# VoltageReferenceProgrammableRevD.net
KiCad netlist of a schematic drawn in EAGLE
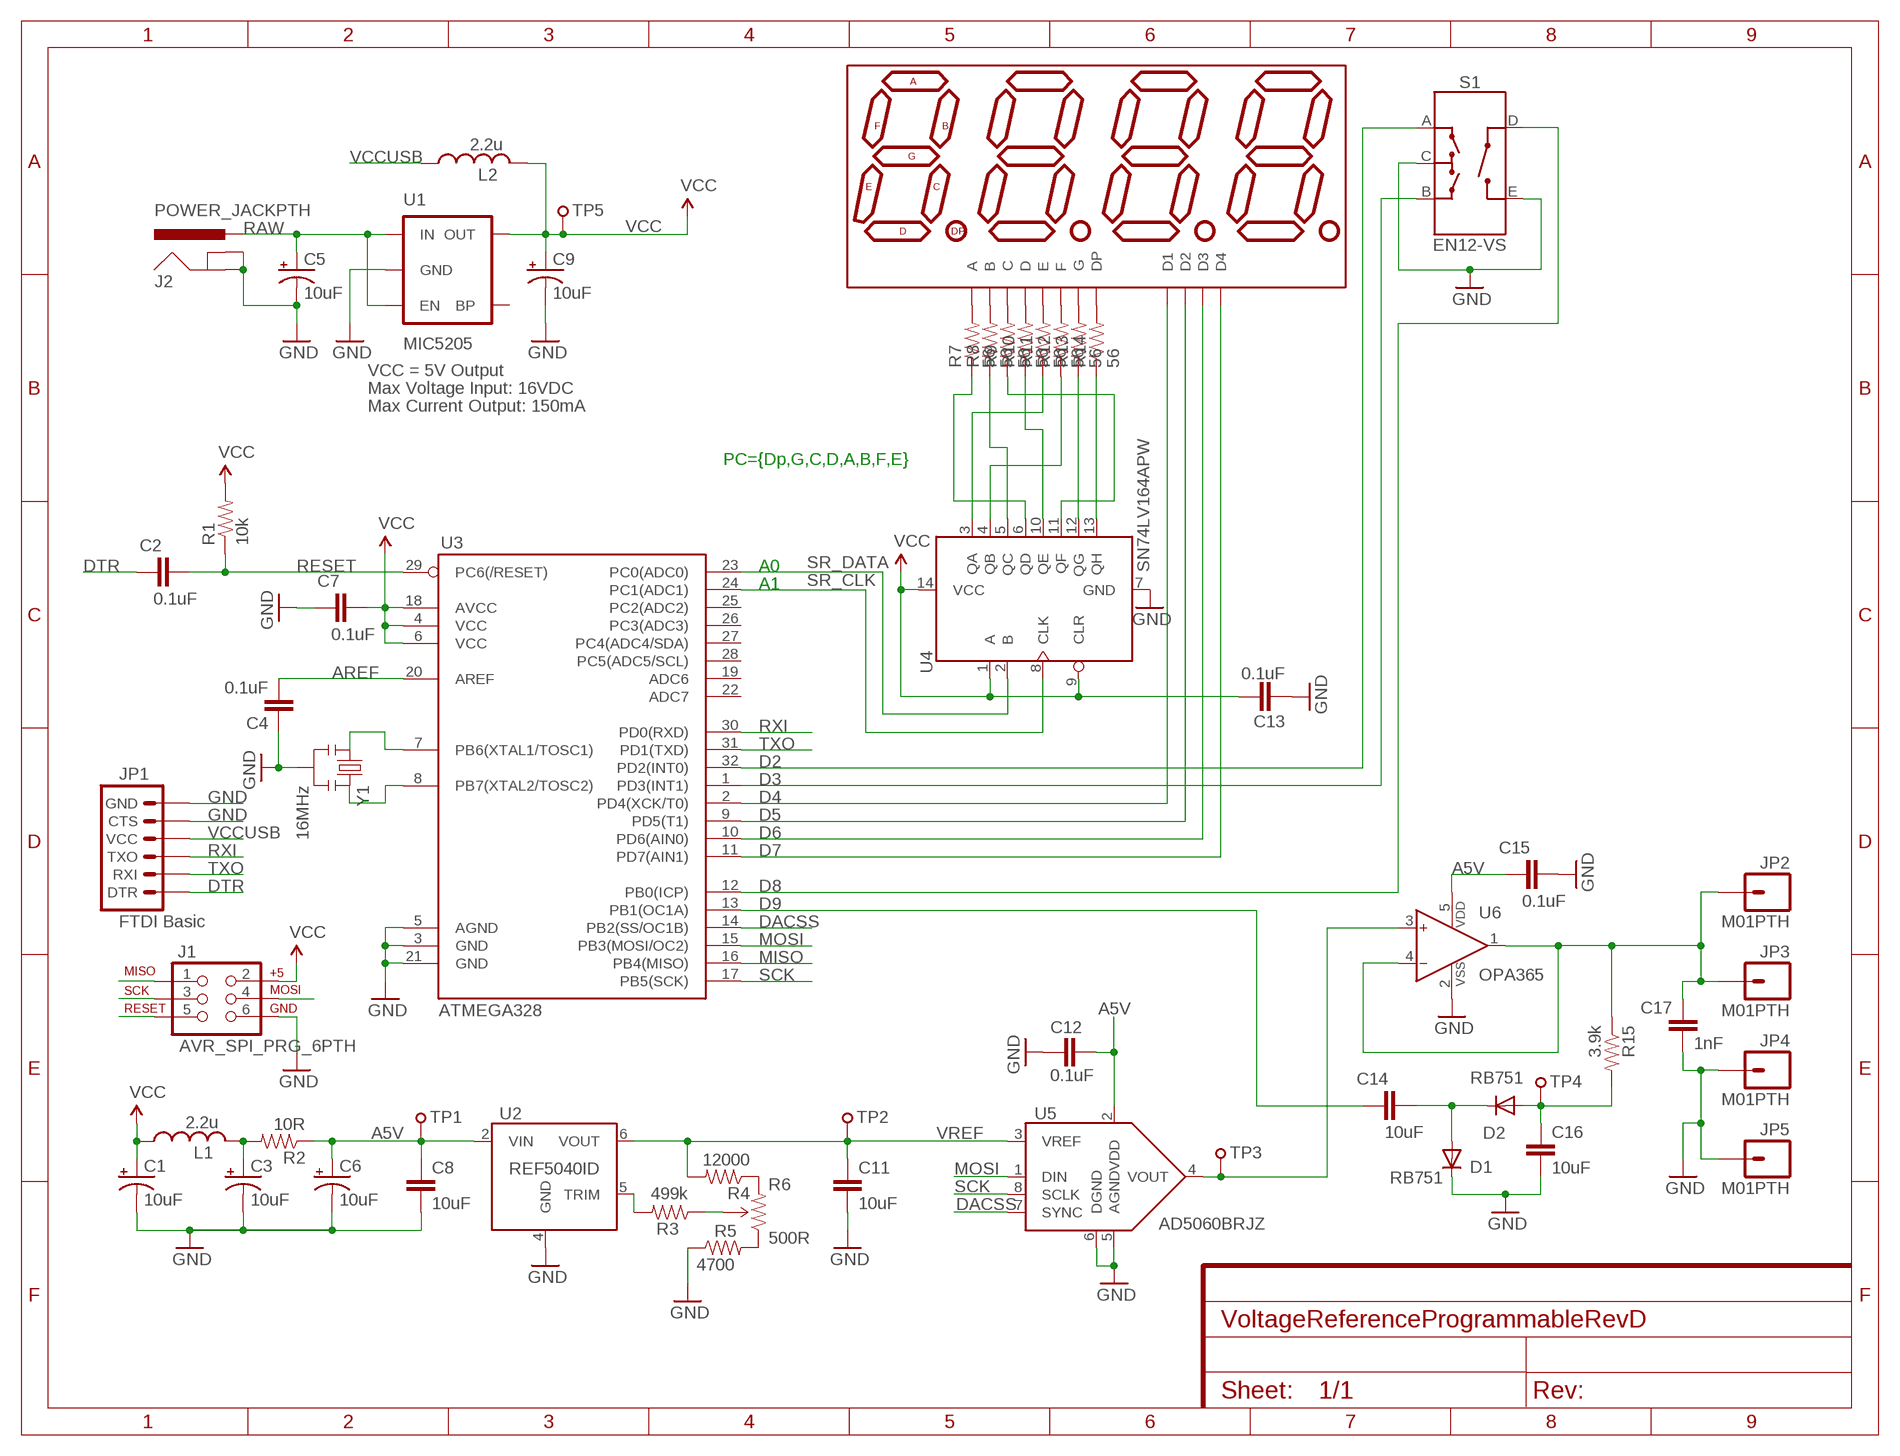
[diagram p0: schematic, sheet 1]

(export (version "E")
  (design (tool "Eeschema 10.0.6"))
  (components
    (comp (ref "C1")
      (value "10uF")
      (footprint "eagle-import:0805-POL")
      (libsource (lib "eagle-import") (part "CAP_POL0805"))
    )
    (comp (ref "C2")
      (value "0.1uF")
      (footprint "eagle-import:0805")
      (libsource (lib "eagle-import") (part "CAP0805"))
    )
    (comp (ref "C3")
      (value "10uF")
      (footprint "eagle-import:0805-POL")
      (libsource (lib "eagle-import") (part "CAP_POL0805"))
    )
    (comp (ref "C4")
      (value "0.1uF")
      (footprint "eagle-import:0805")
      (libsource (lib "eagle-import") (part "CAP0805"))
    )
    (comp (ref "C5")
      (value "10uF")
      (footprint "eagle-import:0805-POL")
      (libsource (lib "eagle-import") (part "CAP_POL0805"))
    )
    (comp (ref "C6")
      (value "10uF")
      (footprint "eagle-import:0805-POL")
      (libsource (lib "eagle-import") (part "CAP_POL0805"))
    )
    (comp (ref "C7")
      (value "0.1uF")
      (footprint "eagle-import:0805")
      (libsource (lib "eagle-import") (part "CAP0805"))
    )
    (comp (ref "C8")
      (value "10uF")
      (footprint "eagle-import:0805")
      (libsource (lib "eagle-import") (part "CAP0805"))
    )
    (comp (ref "C9")
      (value "10uF")
      (footprint "eagle-import:0805-POL")
      (libsource (lib "eagle-import") (part "CAP_POL0805"))
    )
    (comp (ref "C11")
      (value "10uF")
      (footprint "eagle-import:0805")
      (libsource (lib "eagle-import") (part "CAP0805"))
    )
    (comp (ref "C12")
      (value "0.1uF")
      (footprint "eagle-import:0805")
      (libsource (lib "eagle-import") (part "CAP0805"))
    )
    (comp (ref "C13")
      (value "0.1uF")
      (footprint "eagle-import:0805")
      (libsource (lib "eagle-import") (part "CAP0805"))
    )
    (comp (ref "C14")
      (value "10uF")
      (footprint "eagle-import:0805")
      (libsource (lib "eagle-import") (part "CAP0805"))
    )
    (comp (ref "C15")
      (value "0.1uF")
      (footprint "eagle-import:0805")
      (libsource (lib "eagle-import") (part "CAP0805"))
    )
    (comp (ref "C16")
      (value "10uF")
      (footprint "eagle-import:0805")
      (libsource (lib "eagle-import") (part "CAP0805"))
    )
    (comp (ref "C17")
      (value "1nF")
      (footprint "eagle-import:0805")
      (libsource (lib "eagle-import") (part "CAP0805"))
    )
    (comp (ref "D1")
      (value "RB751")
      (footprint "eagle-import:SOD-323")
      (libsource (lib "eagle-import") (part "DIODESOD"))
    )
    (comp (ref "D2")
      (value "RB751")
      (footprint "eagle-import:SOD-323")
      (libsource (lib "eagle-import") (part "DIODESOD"))
    )
    (comp (ref "DISP1")
      (value "hp")
      (footprint "eagle-import:DIL12")
      (libsource (lib "eagle-import") (part "7-SEGMENT-4DIGIT-COUNTER-HP-BUBBLE"))
    )
    (comp (ref "FRAME1")
      (value "FRAME_LTR_CU_MARK")
      (footprint "eagle-import:FR-LTR-ON-PCB")
      (fields
        (field (name "CNAME") "C.Schnarel")
        (field (name "CREVISION") "ProgVRef Rev-D")
        (field (name "DESIGNER") "C.Schnarel")
      )
      (libsource (lib "eagle-import") (part "FRAME_LTR_CU_MARK"))
    )
    (comp (ref "J1")
      (value "AVR_SPI_PRG_6PTH")
      (footprint "eagle-import:2X3")
      (libsource (lib "eagle-import") (part "AVR_SPI_PRG_6PTH"))
    )
    (comp (ref "J2")
      (value "POWER_JACKPTH")
      (footprint "eagle-import:POWER_JACK_PTH")
      (libsource (lib "eagle-import") (part "POWER_JACKPTH"))
    )
    (comp (ref "JP1")
      (value "FTDI Basic")
      (footprint "eagle-import:1X06")
      (libsource (lib "eagle-import") (part "ARDUINO_SERIAL_PROGRAMPTH"))
    )
    (comp (ref "JP2")
      (value "M01PTH")
      (footprint "eagle-import:1X01")
      (libsource (lib "eagle-import") (part "M01PTH"))
    )
    (comp (ref "JP3")
      (value "M01PTH")
      (footprint "eagle-import:1X01")
      (libsource (lib "eagle-import") (part "M01PTH"))
    )
    (comp (ref "JP4")
      (value "M01PTH")
      (footprint "eagle-import:1X01")
      (libsource (lib "eagle-import") (part "M01PTH"))
    )
    (comp (ref "JP5")
      (value "M01PTH")
      (footprint "eagle-import:1X01")
      (libsource (lib "eagle-import") (part "M01PTH"))
    )
    (comp (ref "L1")
      (value "2.2u")
      (footprint "eagle-import:0805")
      (libsource (lib "eagle-import") (part "INDUCTOR"))
    )
    (comp (ref "L2")
      (value "2.2u")
      (footprint "eagle-import:0805")
      (libsource (lib "eagle-import") (part "INDUCTOR"))
    )
    (comp (ref "R1")
      (value "10k")
      (footprint "eagle-import:0805")
      (libsource (lib "eagle-import") (part "RESISTOR0805-RES"))
    )
    (comp (ref "R2")
      (value "10R")
      (footprint "eagle-import:0805")
      (libsource (lib "eagle-import") (part "RESISTOR0805-RES"))
    )
    (comp (ref "R3")
      (value "499k")
      (footprint "eagle-import:0805")
      (libsource (lib "eagle-import") (part "RESISTOR0805-RES"))
    )
    (comp (ref "R4")
      (value "12000")
      (footprint "eagle-import:0805")
      (libsource (lib "eagle-import") (part "RESISTOR0805-RES"))
    )
    (comp (ref "R5")
      (value "4700")
      (footprint "eagle-import:0805")
      (libsource (lib "eagle-import") (part "RESISTOR0805-RES"))
    )
    (comp (ref "R6")
      (value "500R")
      (footprint "eagle-import:T93YB")
      (libsource (lib "eagle-import") (part "TRIMPOT"))
    )
    (comp (ref "R7")
      (value "56")
      (footprint "eagle-import:0805")
      (libsource (lib "eagle-import") (part "RESISTOR0805-RES"))
    )
    (comp (ref "R8")
      (value "56")
      (footprint "eagle-import:0805")
      (libsource (lib "eagle-import") (part "RESISTOR0805-RES"))
    )
    (comp (ref "R9")
      (value "56")
      (footprint "eagle-import:0805")
      (libsource (lib "eagle-import") (part "RESISTOR0805-RES"))
    )
    (comp (ref "R10")
      (value "56")
      (footprint "eagle-import:0805")
      (libsource (lib "eagle-import") (part "RESISTOR0805-RES"))
    )
    (comp (ref "R11")
      (value "56")
      (footprint "eagle-import:0805")
      (libsource (lib "eagle-import") (part "RESISTOR0805-RES"))
    )
    (comp (ref "R12")
      (value "56")
      (footprint "eagle-import:0805")
      (libsource (lib "eagle-import") (part "RESISTOR0805-RES"))
    )
    (comp (ref "R13")
      (value "56")
      (footprint "eagle-import:0805")
      (libsource (lib "eagle-import") (part "RESISTOR0805-RES"))
    )
    (comp (ref "R14")
      (value "56")
      (footprint "eagle-import:0805")
      (libsource (lib "eagle-import") (part "RESISTOR0805-RES"))
    )
    (comp (ref "R15")
      (value "3.9k")
      (footprint "eagle-import:0805")
      (libsource (lib "eagle-import") (part "RESISTOR0805-RES"))
    )
    (comp (ref "S1")
      (value "EN12-VS")
      (footprint "eagle-import:ROTARY_ENCODER_SIDE")
      (libsource (lib "eagle-import") (part "EN12-VS"))
    )
    (comp (ref "TP1")
      (value "TEST_POINT")
      (footprint "eagle-import:BBD-VIA")
      (libsource (lib "eagle-import") (part "TEST_POINT"))
    )
    (comp (ref "TP2")
      (value "TEST_POINT")
      (footprint "eagle-import:BBD-VIA")
      (libsource (lib "eagle-import") (part "TEST_POINT"))
    )
    (comp (ref "TP3")
      (value "TEST_POINT")
      (footprint "eagle-import:BBD-VIA")
      (libsource (lib "eagle-import") (part "TEST_POINT"))
    )
    (comp (ref "TP4")
      (value "TEST_POINT")
      (footprint "eagle-import:BBD-VIA")
      (libsource (lib "eagle-import") (part "TEST_POINT"))
    )
    (comp (ref "TP5")
      (value "TEST_POINT")
      (footprint "eagle-import:BBD-VIA")
      (libsource (lib "eagle-import") (part "TEST_POINT"))
    )
    (comp (ref "U1")
      (value "MIC5205")
      (footprint "eagle-import:SOT23-5")
      (libsource (lib "eagle-import") (part "V_REG_LDOSMD"))
    )
    (comp (ref "U2")
      (value "REF5040ID")
      (footprint "eagle-import:SOIC-8-MINUSPINS")
      (libsource (lib "eagle-import") (part "REF5040ID"))
    )
    (comp (ref "U3")
      (value "ATMEGA328")
      (footprint "eagle-import:TQFP32-08")
      (libsource (lib "eagle-import") (part "ATMEGA168"))
    )
    (comp (ref "U4")
      (value "SN74LV164APW")
      (footprint "eagle-import:TSSOP-14(TI)")
      (libsource (lib "eagle-import") (part "SN74LV164APW"))
    )
    (comp (ref "U5")
      (value "AD5060BRJZ")
      (footprint "eagle-import:SOT-23-8")
      (libsource (lib "eagle-import") (part "AD5040BRJZ"))
    )
    (comp (ref "U6")
      (value "OPA365")
      (footprint "eagle-import:SOT-23-5")
      (libsource (lib "eagle-import") (part "OPA365"))
    )
    (comp (ref "Y1")
      (value "16MHz")
      (footprint "eagle-import:RESONATOR-SMD")
      (libsource (lib "eagle-import") (part "RESONATORSMD"))
    )
  )
  (nets
    (net (code "1") (name "/A5V") (class "Default")
      (node (ref "C12") (pin "1") (pinfunction "1_1") (pintype "passive"))
      (node (ref "C15") (pin "1") (pinfunction "1_1") (pintype "passive"))
      (node (ref "C6") (pin "1") (pinfunction "+_1") (pintype "passive"))
      (node (ref "C8") (pin "1") (pinfunction "1_1") (pintype "passive"))
      (node (ref "R2") (pin "1") (pinfunction "1_1") (pintype "passive"))
      (node (ref "TP1") (pin "P$1") (pinfunction "P$1_P$1") (pintype "bidirectional"))
      (node (ref "U2") (pin "2") (pinfunction "VIN_2") (pintype "bidirectional"))
      (node (ref "U5") (pin "2") (pinfunction "VDD_2") (pintype "bidirectional"))
      (node (ref "U6") (pin "5") (pinfunction "VDD_5") (pintype "power_in"))
    )
    (net (code "2") (name "/AREF") (class "Default")
      (node (ref "C4") (pin "2") (pinfunction "2_2") (pintype "passive"))
      (node (ref "U3") (pin "20") (pinfunction "AREF_20") (pintype "bidirectional"))
    )
    (net (code "3") (name "/D2") (class "Default")
      (node (ref "S1") (pin "A") (pinfunction "A_A") (pintype "bidirectional"))
      (node (ref "U3") (pin "32") (pinfunction "PD2(INT0)_32") (pintype "bidirectional"))
    )
    (net (code "4") (name "/D3") (class "Default")
      (node (ref "S1") (pin "B") (pinfunction "B_B") (pintype "bidirectional"))
      (node (ref "U3") (pin "1") (pinfunction "PD3(INT1)_1") (pintype "bidirectional"))
    )
    (net (code "5") (name "/D4") (class "Default")
      (node (ref "DISP1") (pin "1") (pinfunction "D1_1") (pintype "bidirectional"))
      (node (ref "U3") (pin "2") (pinfunction "PD4(XCK/T0)_2") (pintype "bidirectional"))
    )
    (net (code "6") (name "/D5") (class "Default")
      (node (ref "DISP1") (pin "10") (pinfunction "D2_10") (pintype "bidirectional"))
      (node (ref "U3") (pin "9") (pinfunction "PD5(T1)_9") (pintype "bidirectional"))
    )
    (net (code "7") (name "/D6") (class "Default")
      (node (ref "DISP1") (pin "4") (pinfunction "D3_4") (pintype "bidirectional"))
      (node (ref "U3") (pin "10") (pinfunction "PD6(AIN0)_10") (pintype "bidirectional"))
    )
    (net (code "8") (name "/D7") (class "Default")
      (node (ref "DISP1") (pin "6") (pinfunction "D4_6") (pintype "bidirectional"))
      (node (ref "U3") (pin "11") (pinfunction "PD7(AIN1)_11") (pintype "bidirectional"))
    )
    (net (code "9") (name "/D8") (class "Default")
      (node (ref "S1") (pin "D") (pinfunction "P$1_D") (pintype "bidirectional"))
      (node (ref "U3") (pin "12") (pinfunction "PB0(ICP)_12") (pintype "bidirectional"))
    )
    (net (code "10") (name "/D9") (class "Default")
      (node (ref "C14") (pin "1") (pinfunction "1_1") (pintype "passive"))
      (node (ref "U3") (pin "13") (pinfunction "PB1(OC1A)_13") (pintype "bidirectional"))
    )
    (net (code "11") (name "/DACSS") (class "Default")
      (node (ref "U3") (pin "14") (pinfunction "PB2(SS/OC1B)_14") (pintype "bidirectional"))
      (node (ref "U5") (pin "7") (pinfunction "SYNC_7") (pintype "bidirectional"))
    )
    (net (code "12") (name "/DTR") (class "Default")
      (node (ref "C2") (pin "1") (pinfunction "1_1") (pintype "passive"))
      (node (ref "JP1") (pin "1") (pinfunction "DTR_1") (pintype "passive"))
    )
    (net (code "13") (name "/MISO") (class "Default")
      (node (ref "J1") (pin "1") (pinfunction "1_1") (pintype "passive"))
      (node (ref "U3") (pin "16") (pinfunction "PB4(MISO)_16") (pintype "bidirectional"))
    )
    (net (code "14") (name "/MOSI") (class "Default")
      (node (ref "J1") (pin "4") (pinfunction "4_4") (pintype "passive"))
      (node (ref "U3") (pin "15") (pinfunction "PB3(MOSI/OC2)_15") (pintype "bidirectional"))
      (node (ref "U5") (pin "1") (pinfunction "DIN_1") (pintype "bidirectional"))
    )
    (net (code "15") (name "/RAW") (class "Default")
      (node (ref "C5") (pin "1") (pinfunction "+_1") (pintype "passive"))
      (node (ref "J2") (pin "PWR") (pinfunction "PWR_PWR") (pintype "bidirectional"))
      (node (ref "U1") (pin "1") (pinfunction "IN_1") (pintype "input"))
      (node (ref "U1") (pin "3") (pinfunction "EN_3") (pintype "input"))
    )
    (net (code "16") (name "/RESET") (class "Default")
      (node (ref "C2") (pin "2") (pinfunction "2_2") (pintype "passive"))
      (node (ref "J1") (pin "5") (pinfunction "5_5") (pintype "passive"))
      (node (ref "R1") (pin "1") (pinfunction "1_1") (pintype "passive"))
      (node (ref "U3") (pin "29") (pinfunction "PC6(/RESET)_29") (pintype "bidirectional"))
    )
    (net (code "17") (name "/RXI") (class "Default")
      (node (ref "JP1") (pin "3") (pinfunction "TXO_3") (pintype "passive"))
      (node (ref "U3") (pin "30") (pinfunction "PD0(RXD)_30") (pintype "bidirectional"))
    )
    (net (code "18") (name "/SCK") (class "Default")
      (node (ref "J1") (pin "3") (pinfunction "3_3") (pintype "passive"))
      (node (ref "U3") (pin "17") (pinfunction "PB5(SCK)_17") (pintype "bidirectional"))
      (node (ref "U5") (pin "8") (pinfunction "SCLK_8") (pintype "bidirectional"))
    )
    (net (code "19") (name "/SR_CLK") (class "Default")
      (node (ref "U3") (pin "24") (pinfunction "PC1(ADC1)_24") (pintype "bidirectional"))
      (node (ref "U4") (pin "8") (pinfunction "CLK_8") (pintype "input"))
    )
    (net (code "20") (name "/SR_DATA") (class "Default")
      (node (ref "U3") (pin "23") (pinfunction "PC0(ADC0)_23") (pintype "bidirectional"))
      (node (ref "U4") (pin "2") (pinfunction "B_2") (pintype "input"))
    )
    (net (code "21") (name "/TXO") (class "Default")
      (node (ref "JP1") (pin "2") (pinfunction "RXI_2") (pintype "passive"))
      (node (ref "U3") (pin "31") (pinfunction "PD1(TXD)_31") (pintype "bidirectional"))
    )
    (net (code "22") (name "/VCCUSB") (class "Default")
      (node (ref "JP1") (pin "4") (pinfunction "VCC_4") (pintype "passive"))
      (node (ref "L2") (pin "1") (pinfunction "1_1") (pintype "passive"))
    )
    (net (code "23") (name "/VREF") (class "Default")
      (node (ref "C11") (pin "1") (pinfunction "1_1") (pintype "passive"))
      (node (ref "R4") (pin "2") (pinfunction "2_2") (pintype "passive"))
      (node (ref "TP2") (pin "P$1") (pinfunction "P$1_P$1") (pintype "bidirectional"))
      (node (ref "U2") (pin "6") (pinfunction "VOUT_6") (pintype "bidirectional"))
      (node (ref "U5") (pin "3") (pinfunction "VREF_3") (pintype "bidirectional"))
    )
    (net (code "24") (name "GND") (class "Default")
      (node (ref "C1") (pin "2") (pinfunction "-_2") (pintype "passive"))
      (node (ref "C11") (pin "2") (pinfunction "2_2") (pintype "passive"))
      (node (ref "C12") (pin "2") (pinfunction "2_2") (pintype "passive"))
      (node (ref "C13") (pin "2") (pinfunction "2_2") (pintype "passive"))
      (node (ref "C15") (pin "2") (pinfunction "2_2") (pintype "passive"))
      (node (ref "C16") (pin "2") (pinfunction "2_2") (pintype "passive"))
      (node (ref "C17") (pin "1") (pinfunction "1_1") (pintype "passive"))
      (node (ref "C3") (pin "2") (pinfunction "-_2") (pintype "passive"))
      (node (ref "C4") (pin "1") (pinfunction "1_1") (pintype "passive"))
      (node (ref "C5") (pin "2") (pinfunction "-_2") (pintype "passive"))
      (node (ref "C6") (pin "2") (pinfunction "-_2") (pintype "passive"))
      (node (ref "C7") (pin "1") (pinfunction "1_1") (pintype "passive"))
      (node (ref "C8") (pin "2") (pinfunction "2_2") (pintype "passive"))
      (node (ref "C9") (pin "2") (pinfunction "-_2") (pintype "passive"))
      (node (ref "D1") (pin "1") (pinfunction "C_1") (pintype "passive"))
      (node (ref "J1") (pin "6") (pinfunction "6_6") (pintype "passive"))
      (node (ref "J2") (pin "GND") (pinfunction "GND_GND") (pintype "bidirectional"))
      (node (ref "J2") (pin "GNDBREAK") (pinfunction "GNDBREAK_GNDBREAK") (pintype "bidirectional"))
      (node (ref "JP1") (pin "5") (pinfunction "CTS_5") (pintype "passive"))
      (node (ref "JP1") (pin "6") (pinfunction "GND_6") (pintype "passive"))
      (node (ref "JP4") (pin "1") (pinfunction "1_1") (pintype "passive"))
      (node (ref "JP5") (pin "1") (pinfunction "1_1") (pintype "passive"))
      (node (ref "R5") (pin "1") (pinfunction "1_1") (pintype "passive"))
      (node (ref "S1") (pin "C") (pinfunction "C_C") (pintype "bidirectional"))
      (node (ref "S1") (pin "E") (pinfunction "P$2_E") (pintype "bidirectional"))
      (node (ref "U1") (pin "2") (pinfunction "GND_2") (pintype "input"))
      (node (ref "U2") (pin "4") (pinfunction "GND_4") (pintype "bidirectional"))
      (node (ref "U3") (pin "21") (pinfunction "GND_21") (pintype "bidirectional"))
      (node (ref "U3") (pin "3") (pinfunction "GND_3") (pintype "bidirectional"))
      (node (ref "U3") (pin "5") (pinfunction "AGND_5") (pintype "bidirectional"))
      (node (ref "U4") (pin "7") (pinfunction "GND_7") (pintype "power_in"))
      (node (ref "U5") (pin "5") (pinfunction "AGND_5") (pintype "bidirectional"))
      (node (ref "U5") (pin "6") (pinfunction "DGND_6") (pintype "bidirectional"))
      (node (ref "U6") (pin "2") (pinfunction "VSS_2") (pintype "power_in"))
      (node (ref "Y1") (pin "2") (pinfunction "2_2") (pintype "passive"))
    )
    (net (code "25") (name "Net-(C3-+)") (class "Default")
      (node (ref "C3") (pin "1") (pinfunction "+_1") (pintype "passive"))
      (node (ref "L1") (pin "2") (pinfunction "2_2") (pintype "passive"))
      (node (ref "R2") (pin "2") (pinfunction "2_2") (pintype "passive"))
    )
    (net (code "26") (name "Net-(D1-A)") (class "Default")
      (node (ref "C14") (pin "2") (pinfunction "2_2") (pintype "passive"))
      (node (ref "D1") (pin "2") (pinfunction "A_2") (pintype "passive"))
      (node (ref "D2") (pin "1") (pinfunction "C_1") (pintype "passive"))
    )
    (net (code "27") (name "Net-(D2-A)") (class "Default")
      (node (ref "C16") (pin "1") (pinfunction "1_1") (pintype "passive"))
      (node (ref "D2") (pin "2") (pinfunction "A_2") (pintype "passive"))
      (node (ref "R15") (pin "2") (pinfunction "2_2") (pintype "passive"))
      (node (ref "TP4") (pin "P$1") (pinfunction "P$1_P$1") (pintype "bidirectional"))
    )
    (net (code "28") (name "Net-(DISP1-A)") (class "Default")
      (node (ref "DISP1") (pin "12") (pinfunction "A_12") (pintype "bidirectional"))
      (node (ref "R7") (pin "2") (pinfunction "2_2") (pintype "passive"))
    )
    (net (code "29") (name "Net-(DISP1-B)") (class "Default")
      (node (ref "DISP1") (pin "11") (pinfunction "B_11") (pintype "bidirectional"))
      (node (ref "R8") (pin "2") (pinfunction "2_2") (pintype "passive"))
    )
    (net (code "30") (name "Net-(DISP1-C)") (class "Default")
      (node (ref "DISP1") (pin "3") (pinfunction "C_3") (pintype "bidirectional"))
      (node (ref "R9") (pin "2") (pinfunction "2_2") (pintype "passive"))
    )
    (net (code "31") (name "Net-(DISP1-D)") (class "Default")
      (node (ref "DISP1") (pin "8") (pinfunction "D_8") (pintype "bidirectional"))
      (node (ref "R10") (pin "2") (pinfunction "2_2") (pintype "passive"))
    )
    (net (code "32") (name "Net-(DISP1-DP)") (class "Default")
      (node (ref "DISP1") (pin "5") (pinfunction "DP_5") (pintype "bidirectional"))
      (node (ref "R14") (pin "2") (pinfunction "2_2") (pintype "passive"))
    )
    (net (code "33") (name "Net-(DISP1-E)") (class "Default")
      (node (ref "DISP1") (pin "2") (pinfunction "E_2") (pintype "bidirectional"))
      (node (ref "R11") (pin "2") (pinfunction "2_2") (pintype "passive"))
    )
    (net (code "34") (name "Net-(DISP1-F)") (class "Default")
      (node (ref "DISP1") (pin "9") (pinfunction "F_9") (pintype "bidirectional"))
      (node (ref "R12") (pin "2") (pinfunction "2_2") (pintype "passive"))
    )
    (net (code "35") (name "Net-(DISP1-G)") (class "Default")
      (node (ref "DISP1") (pin "7") (pinfunction "G_7") (pintype "bidirectional"))
      (node (ref "R13") (pin "2") (pinfunction "2_2") (pintype "passive"))
    )
    (net (code "36") (name "Net-(R6-CCW)") (class "Default")
      (node (ref "R5") (pin "2") (pinfunction "2_2") (pintype "passive"))
      (node (ref "R6") (pin "1") (pinfunction "CCW_1") (pintype "passive"))
    )
    (net (code "37") (name "Net-(R6-CW)") (class "Default")
      (node (ref "R4") (pin "1") (pinfunction "1_1") (pintype "passive"))
      (node (ref "R6") (pin "3") (pinfunction "CW_3") (pintype "passive"))
    )
    (net (code "38") (name "Net-(R6-WIPER)") (class "Default")
      (node (ref "R3") (pin "1") (pinfunction "1_1") (pintype "passive"))
      (node (ref "R6") (pin "2") (pinfunction "WIPER_2") (pintype "passive"))
    )
    (net (code "39") (name "Net-(U2-TRIM)") (class "Default")
      (node (ref "R3") (pin "2") (pinfunction "2_2") (pintype "passive"))
      (node (ref "U2") (pin "5") (pinfunction "TRIM_5") (pintype "bidirectional"))
    )
    (net (code "40") (name "Net-(U3-PB6(XTAL1{slash}TOSC1))") (class "Default")
      (node (ref "U3") (pin "7") (pinfunction "PB6(XTAL1/TOSC1)_7") (pintype "bidirectional"))
      (node (ref "Y1") (pin "1") (pinfunction "1_1") (pintype "passive"))
    )
    (net (code "41") (name "Net-(U3-PB7(XTAL2{slash}TOSC2))") (class "Default")
      (node (ref "U3") (pin "8") (pinfunction "PB7(XTAL2/TOSC2)_8") (pintype "bidirectional"))
      (node (ref "Y1") (pin "3") (pinfunction "3_3") (pintype "passive"))
    )
    (net (code "42") (name "Net-(U4-QA)") (class "Default")
      (node (ref "R11") (pin "1") (pinfunction "1_1") (pintype "passive"))
      (node (ref "U4") (pin "3") (pinfunction "QA_3") (pintype "bidirectional"))
    )
    (net (code "43") (name "Net-(U4-QB)") (class "Default")
      (node (ref "R12") (pin "1") (pinfunction "1_1") (pintype "passive"))
      (node (ref "U4") (pin "4") (pinfunction "QB_4") (pintype "bidirectional"))
    )
    (net (code "44") (name "Net-(U4-QC)") (class "Default")
      (node (ref "R8") (pin "1") (pinfunction "1_1") (pintype "passive"))
      (node (ref "U4") (pin "5") (pinfunction "QC_5") (pintype "bidirectional"))
    )
    (net (code "45") (name "Net-(U4-QD)") (class "Default")
      (node (ref "R7") (pin "1") (pinfunction "1_1") (pintype "passive"))
      (node (ref "U4") (pin "6") (pinfunction "QD_6") (pintype "bidirectional"))
    )
    (net (code "46") (name "Net-(U4-QE)") (class "Default")
      (node (ref "R10") (pin "1") (pinfunction "1_1") (pintype "passive"))
      (node (ref "U4") (pin "10") (pinfunction "QE_10") (pintype "bidirectional"))
    )
    (net (code "47") (name "Net-(U4-QF)") (class "Default")
      (node (ref "R9") (pin "1") (pinfunction "1_1") (pintype "passive"))
      (node (ref "U4") (pin "11") (pinfunction "QF_11") (pintype "bidirectional"))
    )
    (net (code "48") (name "Net-(U4-QG)") (class "Default")
      (node (ref "R13") (pin "1") (pinfunction "1_1") (pintype "passive"))
      (node (ref "U4") (pin "12") (pinfunction "QG_12") (pintype "bidirectional"))
    )
    (net (code "49") (name "Net-(U4-QH)") (class "Default")
      (node (ref "R14") (pin "1") (pinfunction "1_1") (pintype "passive"))
      (node (ref "U4") (pin "13") (pinfunction "QH_13") (pintype "bidirectional"))
    )
    (net (code "50") (name "Net-(U5-VOUT)") (class "Default")
      (node (ref "TP3") (pin "P$1") (pinfunction "P$1_P$1") (pintype "bidirectional"))
      (node (ref "U5") (pin "4") (pinfunction "VOUT_4") (pintype "bidirectional"))
      (node (ref "U6") (pin "3") (pinfunction "IN+_3") (pintype "input"))
    )
    (net (code "51") (name "Net-(U6-IN-)") (class "Default")
      (node (ref "C17") (pin "2") (pinfunction "2_2") (pintype "passive"))
      (node (ref "JP2") (pin "1") (pinfunction "1_1") (pintype "passive"))
      (node (ref "JP3") (pin "1") (pinfunction "1_1") (pintype "passive"))
      (node (ref "R15") (pin "1") (pinfunction "1_1") (pintype "passive"))
      (node (ref "U6") (pin "1") (pinfunction "OUT_1") (pintype "output"))
      (node (ref "U6") (pin "4") (pinfunction "IN-_4") (pintype "input"))
    )
    (net (code "52") (name "VCC") (class "Default")
      (node (ref "C1") (pin "1") (pinfunction "+_1") (pintype "passive"))
      (node (ref "C13") (pin "1") (pinfunction "1_1") (pintype "passive"))
      (node (ref "C7") (pin "2") (pinfunction "2_2") (pintype "passive"))
      (node (ref "C9") (pin "1") (pinfunction "+_1") (pintype "passive"))
      (node (ref "J1") (pin "2") (pinfunction "2_2") (pintype "passive"))
      (node (ref "L1") (pin "1") (pinfunction "1_1") (pintype "passive"))
      (node (ref "L2") (pin "2") (pinfunction "2_2") (pintype "passive"))
      (node (ref "R1") (pin "2") (pinfunction "2_2") (pintype "passive"))
      (node (ref "TP5") (pin "P$1") (pinfunction "P$1_P$1") (pintype "bidirectional"))
      (node (ref "U1") (pin "5") (pinfunction "OUT_5") (pintype "passive"))
      (node (ref "U3") (pin "18") (pinfunction "AVCC_18") (pintype "bidirectional"))
      (node (ref "U3") (pin "4") (pinfunction "VCC_4") (pintype "bidirectional"))
      (node (ref "U3") (pin "6") (pinfunction "VCC_6") (pintype "bidirectional"))
      (node (ref "U4") (pin "1") (pinfunction "A_1") (pintype "bidirectional"))
      (node (ref "U4") (pin "14") (pinfunction "VCC_14") (pintype "power_in"))
      (node (ref "U4") (pin "9") (pinfunction "CLR_9") (pintype "bidirectional"))
    )
    (net (code "53") (name "unconnected-(U1-BP-Pad4)") (class "Default")
      (node (ref "U1") (pin "4") (pinfunction "BP_4") (pintype "input"))
    )
    (net (code "54") (name "unconnected-(U3-ADC6-Pad19)") (class "Default")
      (node (ref "U3") (pin "19") (pinfunction "ADC6_19") (pintype "bidirectional"))
    )
    (net (code "55") (name "unconnected-(U3-ADC7-Pad22)") (class "Default")
      (node (ref "U3") (pin "22") (pinfunction "ADC7_22") (pintype "bidirectional"))
    )
    (net (code "56") (name "unconnected-(U3-PC2(ADC2)-Pad25)") (class "Default")
      (node (ref "U3") (pin "25") (pinfunction "PC2(ADC2)_25") (pintype "bidirectional"))
    )
    (net (code "57") (name "unconnected-(U3-PC3(ADC3)-Pad26)") (class "Default")
      (node (ref "U3") (pin "26") (pinfunction "PC3(ADC3)_26") (pintype "bidirectional"))
    )
    (net (code "58") (name "unconnected-(U3-PC4(ADC4{slash}SDA)-Pad27)") (class "Default")
      (node (ref "U3") (pin "27") (pinfunction "PC4(ADC4/SDA)_27") (pintype "bidirectional"))
    )
    (net (code "59") (name "unconnected-(U3-PC5(ADC5{slash}SCL)-Pad28)") (class "Default")
      (node (ref "U3") (pin "28") (pinfunction "PC5(ADC5/SCL)_28") (pintype "bidirectional"))
    )
  )
)
